# main.net
KiCad netlist of a schematic drawn in Altium Designer
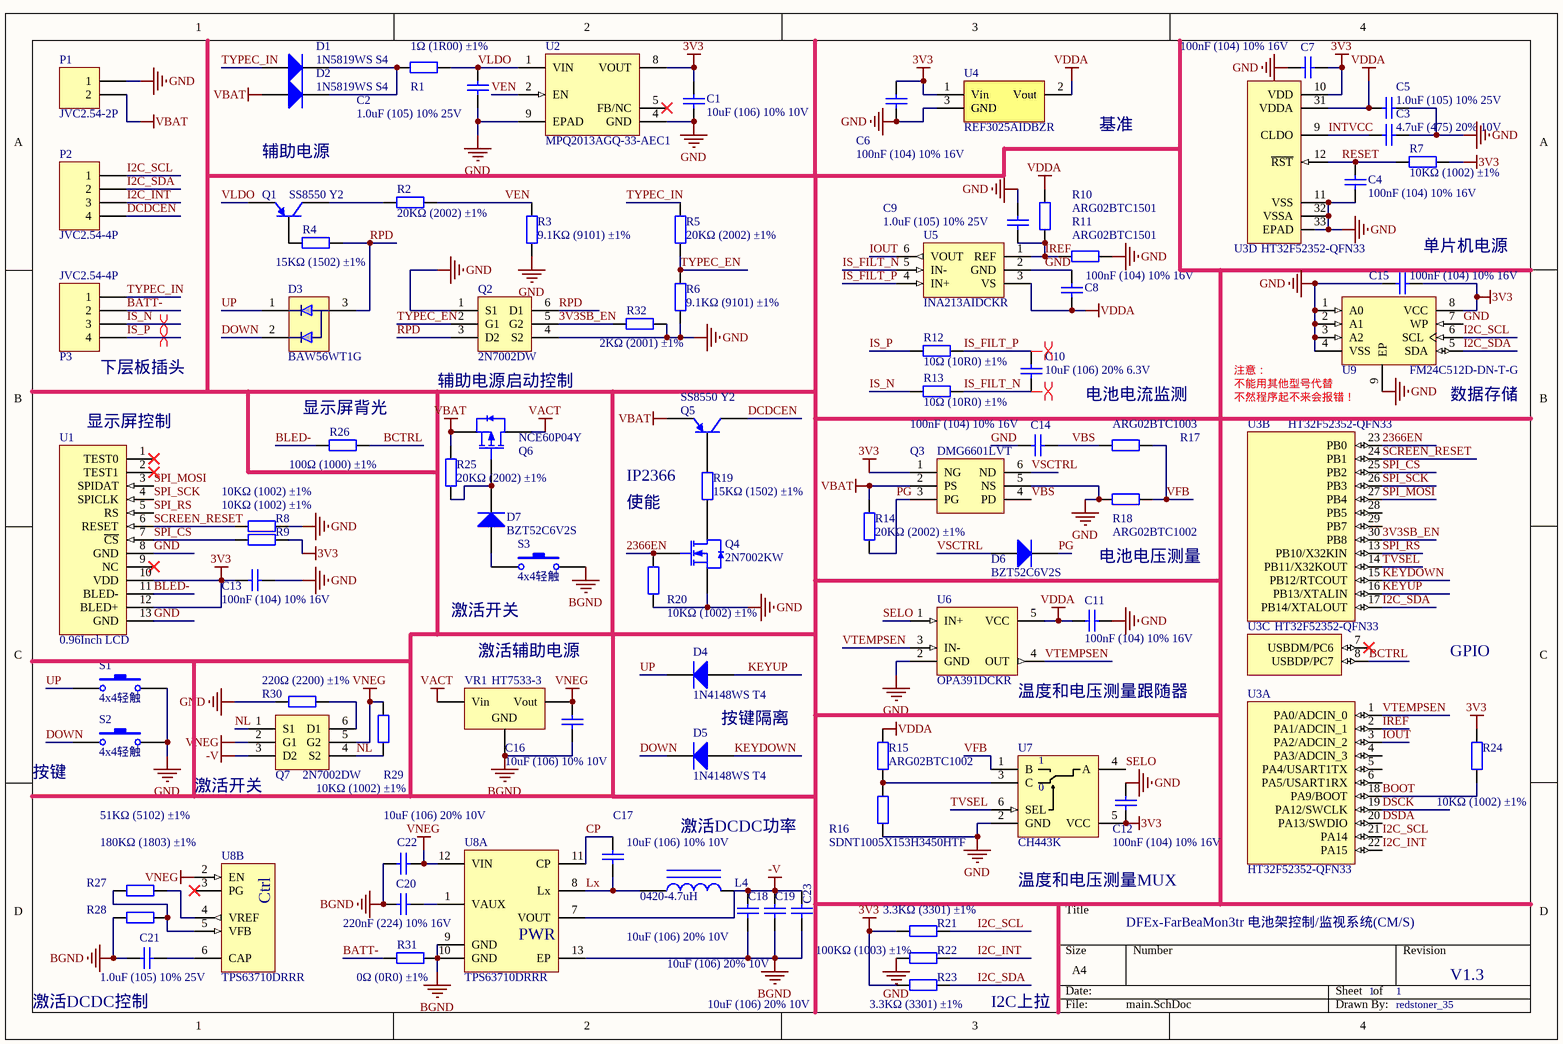
[diagram p0: main.SchDoc]

(export (version "E")
  (design (tool "Eeschema 10.0.6"))
  (components
    (comp (ref "C1")
      (value "10uF (106) 10% 10V")
      (footprint "0603_C")
      (description "贴片电容")
      (libsource (lib "Miscellaneous Devices LC") (part "0603 10uF (106) 10% 10V"))
    )
    (comp (ref "C2")
      (value "1.0uF (105) 10% 25V")
      (footprint "0402_C")
      (description "贴片电容")
      (libsource (lib "Miscellaneous Devices LC") (part "0402 1.0uF (105) 10% 25V"))
    )
    (comp (ref "C3")
      (value "4.7uF (475) 20% 10V")
      (footprint "0402_C")
      (description "贴片电容")
      (libsource (lib "Miscellaneous Devices LC") (part "0402 4.7uF (475) 20% 10V"))
    )
    (comp (ref "C4")
      (value "100nF (104) 10% 16V")
      (footprint "0402_C")
      (description "贴片电容")
      (libsource (lib "Miscellaneous Devices LC") (part "0402 100nF (104) 10% 16V"))
    )
    (comp (ref "C5")
      (value "1.0uF (105) 10% 25V")
      (footprint "0402_C")
      (description "贴片电容")
      (libsource (lib "Miscellaneous Devices LC") (part "0402 1.0uF (105) 10% 25V"))
    )
    (comp (ref "C6")
      (value "100nF (104) 10% 16V")
      (footprint "0402_C")
      (description "贴片电容")
      (libsource (lib "Miscellaneous Devices LC") (part "0402 100nF (104) 10% 16V"))
    )
    (comp (ref "C7")
      (value "100nF (104) 10% 16V")
      (footprint "0402_C")
      (description "贴片电容")
      (libsource (lib "Miscellaneous Devices LC") (part "0402 100nF (104) 10% 16V"))
    )
    (comp (ref "C8")
      (value "100nF (104) 10% 16V")
      (footprint "0402_C")
      (description "贴片电容")
      (libsource (lib "Miscellaneous Devices LC") (part "0402 100nF (104) 10% 16V"))
    )
    (comp (ref "C9")
      (value "1.0uF (105) 10% 25V")
      (footprint "0402_C")
      (description "贴片电容")
      (libsource (lib "Miscellaneous Devices LC") (part "0402 1.0uF (105) 10% 25V"))
    )
    (comp (ref "C10")
      (value "10uF (106) 20% 6.3V")
      (footprint "0402_C")
      (description "贴片电容")
      (libsource (lib "Miscellaneous Devices LC") (part "0402 10uF (106) 20% 6.3V"))
    )
    (comp (ref "C11")
      (value "100nF (104) 10% 16V")
      (footprint "0402_C")
      (description "贴片电容")
      (libsource (lib "Miscellaneous Devices LC") (part "0402 100nF (104) 10% 16V"))
    )
    (comp (ref "C12")
      (value "100nF (104) 10% 16V")
      (footprint "0402_C")
      (description "贴片电容")
      (libsource (lib "Miscellaneous Devices LC") (part "0402 100nF (104) 10% 16V"))
    )
    (comp (ref "C13")
      (value "100nF (104) 10% 16V")
      (footprint "0402_C")
      (description "贴片电容")
      (libsource (lib "Miscellaneous Devices LC") (part "0402 100nF (104) 10% 16V"))
    )
    (comp (ref "C14")
      (value "100nF (104) 10% 16V")
      (footprint "0402_C")
      (description "贴片电容")
      (libsource (lib "Miscellaneous Devices LC") (part "0402 100nF (104) 10% 16V"))
    )
    (comp (ref "C15")
      (value "100nF (104) 10% 16V")
      (footprint "0402_C")
      (description "贴片电容")
      (libsource (lib "Miscellaneous Devices LC") (part "0402 100nF (104) 10% 16V"))
    )
    (comp (ref "C16")
      (value "10uF (106) 10% 10V")
      (footprint "0603_C")
      (description "贴片电容")
      (libsource (lib "Miscellaneous Devices LC") (part "0603 10uF (106) 10% 10V"))
    )
    (comp (ref "C17")
      (value "10uF (106) 10% 10V")
      (footprint "0603_C")
      (description "贴片电容")
      (libsource (lib "Miscellaneous Devices LC") (part "0603 10uF (106) 10% 10V"))
    )
    (comp (ref "C18")
      (value "10uF (106) 20% 10V")
      (footprint "0402_C")
      (description "贴片电容")
      (libsource (lib "Miscellaneous Devices LC") (part "0402 10uF (106) 20% 6.3V"))
    )
    (comp (ref "C19")
      (value "10uF (106) 20% 10V")
      (footprint "0402_C")
      (description "贴片电容")
      (libsource (lib "Miscellaneous Devices LC") (part "0402 10uF (106) 20% 6.3V"))
    )
    (comp (ref "C20")
      (value "220nF (224) 10% 16V")
      (footprint "0402_C")
      (description "贴片电容")
      (libsource (lib "Miscellaneous Devices LC") (part "0402 220nF (224) 10% 16V"))
    )
    (comp (ref "C21")
      (value "1.0uF (105) 10% 25V")
      (footprint "0402_C")
      (description "贴片电容")
      (libsource (lib "Miscellaneous Devices LC") (part "0402 1.0uF (105) 10% 25V"))
    )
    (comp (ref "C22")
      (value "10uF (106) 20% 10V")
      (footprint "0402_C")
      (description "贴片电容")
      (libsource (lib "Miscellaneous Devices LC") (part "0402 10uF (106) 20% 6.3V"))
    )
    (comp (ref "C23")
      (value "10uF (106) 20% 10V")
      (footprint "0402_C")
      (description "贴片电容")
      (libsource (lib "Miscellaneous Devices LC") (part "0402 10uF (106) 20% 6.3V"))
    )
    (comp (ref "D1")
      (value "1N5819WS S4")
      (footprint "SOD-323")
      (description "二极管")
      (libsource (lib "Miscellaneous Devices LC") (part "SOD-323 1N4148WS T4"))
    )
    (comp (ref "D2")
      (value "1N5819WS S4")
      (footprint "SOD-323")
      (description "二极管")
      (libsource (lib "Miscellaneous Devices LC") (part "SOD-323 1N4148WS T4"))
    )
    (comp (ref "D3")
      (value "BAW56WT1G")
      (footprint "SC70-3")
      (description "Dual Switching diode,common anode,SOT323-3(SC70-3)")
      (libsource (lib "custom") (part "BAW56WT1G"))
    )
    (comp (ref "D4")
      (value "1N4148WS T4")
      (footprint "SOD-323")
      (description "二极管")
      (libsource (lib "Miscellaneous Devices LC") (part "SOD-323 1N4148WS T4"))
    )
    (comp (ref "D5")
      (value "1N4148WS T4")
      (footprint "SOD-323")
      (description "二极管")
      (libsource (lib "Miscellaneous Devices LC") (part "SOD-323 1N4148WS T4"))
    )
    (comp (ref "D6")
      (value "BZT52C6V2S")
      (footprint "SOD-323")
      (description "SOD-323稳压二极管 6.2V稳压电压")
      (libsource (lib "Miscellaneous Devices LC") (part "SOD-323 1N4148WS T4"))
    )
    (comp (ref "D7")
      (value "BZT52C6V2S")
      (footprint "SOD-323")
      (description "SOD-323稳压二极管 6.2V稳压电压")
      (libsource (lib "Miscellaneous Devices LC") (part "SOD-323 1N4148WS T4"))
    )
    (comp (ref "L4")
      (value "0420-4.7uH")
      (footprint "0420CDMCCDS-***MC")
      (description "一体成型贴片电感 4x4x2mm尺寸   4.7uH电感量")
      (fields (field (name "PUBLISHER") "Altium Limited"))
      (libsource (lib "Miscellaneous Devices") (part "Inductor Iron"))
    )
    (comp (ref "P1")
      (value "JVC2.54-2P")
      (footprint "CONN-TH_2P-P2.54_JVC-2.54MM-2P")
      (description "2-Pin")
      (fields (field (name "PUBLISHER") "Altium Limited"))
      (libsource (lib "山猫的集成库20190318") (part "CON 2"))
    )
    (comp (ref "P2")
      (value "JVC2.54-4P")
      (footprint "CONN-TH_4P-P2.54_JVC-2.54MM-4P")
      (description "4-Pin")
      (fields (field (name "PUBLISHER") "Altium Limited"))
      (libsource (lib "山猫的集成库20190318") (part "CON 4"))
    )
    (comp (ref "P3")
      (value "JVC2.54-4P")
      (footprint "CONN-TH_4P-P2.54_JVC-2.54MM-4P")
      (description "4-Pin")
      (fields (field (name "PUBLISHER") "Altium Limited"))
      (libsource (lib "山猫的集成库20190318") (part "CON 4"))
    )
    (comp (ref "Q1")
      (value "SS8550 Y2")
      (footprint "SC70-3")
      (description "PNP三极管，SOT-323 封装")
      (libsource (lib "Miscellaneous Devices LC") (part "SOT-23 SS8550 Y2"))
    )
    (comp (ref "Q2")
      (value "2N7002DW")
      (footprint "SC70-6")
      (description "Dual N-Channel MOSFET 60V340mA SOT-363")
      (libsource (lib "custom") (part "2N7002DW"))
    )
    (comp (ref "Q3")
      (value "DMG6601LVT")
      (footprint "SOT95P245X110-6N")
      (description "SOT23-6 N+P Ch. MOSFET")
      (libsource (lib "custom") (part "DMG6601LVT"))
    )
    (comp (ref "Q4")
      (value "2N7002KW")
      (footprint "SC70-3")
      (description "MOS(场效应管)")
      (libsource (lib "Miscellaneous Devices LC") (part "2N7002 7002"))
    )
    (comp (ref "Q5")
      (value "SS8550 Y2")
      (footprint "SC70-3")
      (description "PNP三极管，SOT-323 封装")
      (libsource (lib "Miscellaneous Devices LC") (part "SOT-23 SS8550 Y2"))
    )
    (comp (ref "Q6")
      (value "NCE60P04Y")
      (footprint "SOT-23(SOT-23-3)")
      (description "MOS(场效应管)")
      (libsource (lib "Miscellaneous Devices LC") (part "SI2301CDS-T1-GE3"))
    )
    (comp (ref "Q7")
      (value "2N7002DW")
      (footprint "SC70-6")
      (description "Dual N-Channel MOSFET 60V340mA SOT-363")
      (libsource (lib "custom") (part "2N7002DW"))
    )
    (comp (ref "R1")
      (value "1Ω (1R00) ±1%")
      (footprint "0402_R")
      (description "贴片电阻")
      (libsource (lib "Miscellaneous Devices LC") (part "0402 1Ω (1R00) 1%"))
    )
    (comp (ref "R2")
      (value "20KΩ (2002) ±1%")
      (footprint "0402_R")
      (description "贴片电阻")
      (libsource (lib "Miscellaneous Devices LC") (part "0402 20KΩ (2002) 1%"))
    )
    (comp (ref "R3")
      (value "9.1KΩ (9101) ±1%")
      (footprint "0402_R")
      (description "贴片电阻")
      (libsource (lib "") (part "0402 10KΩ (1002) 1%_1"))
    )
    (comp (ref "R4")
      (value "15KΩ (1502) ±1%")
      (footprint "0402_R")
      (description "贴片电阻")
      (libsource (lib "") (part "0402 15KΩ (1502) 1%_1"))
    )
    (comp (ref "R5")
      (value "20KΩ (2002) ±1%")
      (footprint "0402_R")
      (description "贴片电阻")
      (libsource (lib "") (part "0402 20KΩ (2002) 1%_1"))
    )
    (comp (ref "R6")
      (value "9.1KΩ (9101) ±1%")
      (footprint "0402_R")
      (description "贴片电阻")
      (libsource (lib "") (part "0402 10KΩ (1002) 1%_1"))
    )
    (comp (ref "R7")
      (value "10KΩ (1002) ±1%")
      (footprint "0402_R")
      (description "贴片电阻")
      (libsource (lib "Miscellaneous Devices LC") (part "0402 10KΩ (1002) 1%"))
    )
    (comp (ref "R8")
      (value "10KΩ (1002) ±1%")
      (footprint "0402_R")
      (description "贴片电阻")
      (libsource (lib "Miscellaneous Devices LC") (part "0402 10KΩ (1002) 1%"))
    )
    (comp (ref "R9")
      (value "10KΩ (1002) ±1%")
      (footprint "0402_R")
      (description "贴片电阻")
      (libsource (lib "Miscellaneous Devices LC") (part "0402 10KΩ (1002) 1%"))
    )
    (comp (ref "R10")
      (value "ARG02BTC1501")
      (footprint "0402_R")
      (description "贴片精密电阻，1.5K 0.1% 25PPM")
      (libsource (lib "") (part "0402 2KΩ (2001) 1%_1"))
    )
    (comp (ref "R11")
      (value "ARG02BTC1501")
      (footprint "0402_R")
      (description "贴片精密电阻，1.5K 0.1% 25PPM")
      (libsource (lib "Miscellaneous Devices LC") (part "0402 2KΩ (2001) 1%"))
    )
    (comp (ref "R12")
      (value "10Ω (10R0) ±1%")
      (footprint "0402_R")
      (description "贴片电阻")
      (libsource (lib "Miscellaneous Devices LC") (part "0402 10Ω (10R0) 1%"))
    )
    (comp (ref "R13")
      (value "10Ω (10R0) ±1%")
      (footprint "0402_R")
      (description "贴片电阻")
      (libsource (lib "Miscellaneous Devices LC") (part "0402 10Ω (10R0) 1%"))
    )
    (comp (ref "R14")
      (value "20KΩ (2002) ±1%")
      (footprint "0402_R")
      (description "贴片电阻")
      (libsource (lib "") (part "0402 20KΩ (2002) 1%_1"))
    )
    (comp (ref "R15")
      (value "ARG02BTC1002")
      (footprint "0402_R")
      (description "贴片精密电阻，10K 0.1% 25PPM")
      (libsource (lib "") (part "0402 10KΩ (1002) 1%_1"))
    )
    (comp (ref "R16")
      (value "SDNT1005X153H3450HTF")
      (footprint "0402_R")
      (description "贴片热敏电阻 15K@25℃ 1% B值3450")
      (libsource (lib "") (part "0402 10KΩ (1002) 1%_1"))
    )
    (comp (ref "R17")
      (value "ARG02BTC1003")
      (footprint "0402_R")
      (description "贴片精密电阻，100K 0.1% 25PPM")
      (libsource (lib "Miscellaneous Devices LC") (part "0402 100KΩ (1003) 1%"))
    )
    (comp (ref "R18")
      (value "ARG02BTC1002")
      (footprint "0402_R")
      (description "贴片精密电阻，10K 0.1% 25PPM")
      (libsource (lib "Miscellaneous Devices LC") (part "0402 10KΩ (1002) 1%"))
    )
    (comp (ref "R19")
      (value "15KΩ (1502) ±1%")
      (footprint "0402_R")
      (description "贴片电阻")
      (libsource (lib "Miscellaneous Devices LC") (part "0402 15KΩ (1502) 1%"))
    )
    (comp (ref "R20")
      (value "10KΩ (1002) ±1%")
      (footprint "0402_R")
      (description "贴片电阻")
      (libsource (lib "") (part "0402 10KΩ (1002) 1%_1"))
    )
    (comp (ref "R21")
      (value "3.3KΩ (3301) ±1%")
      (footprint "0402_R")
      (description "贴片电阻")
      (libsource (lib "Miscellaneous Devices LC") (part "0402 3.3KΩ (3301) 1%"))
    )
    (comp (ref "R22")
      (value "100KΩ (1003) ±1%")
      (footprint "0402_R")
      (description "贴片电阻")
      (libsource (lib "") (part "0402 100KΩ (1003) 1%_1"))
    )
    (comp (ref "R23")
      (value "3.3KΩ (3301) ±1%")
      (footprint "0402_R")
      (description "贴片电阻")
      (libsource (lib "Miscellaneous Devices LC") (part "0402 3.3KΩ (3301) 1%"))
    )
    (comp (ref "R24")
      (value "10KΩ (1002) ±1%")
      (footprint "0402_R")
      (description "贴片电阻")
      (libsource (lib "") (part "0402 10KΩ (1002) 1%_1"))
    )
    (comp (ref "R25")
      (value "20KΩ (2002) ±1%")
      (footprint "0402_R")
      (description "贴片电阻")
      (libsource (lib "") (part "0402 20KΩ (2002) 1%_1"))
    )
    (comp (ref "R26")
      (value "100Ω (1000) ±1%")
      (footprint "0402_R")
      (description "贴片电阻")
      (libsource (lib "Miscellaneous Devices LC") (part "0402 100Ω (1000) 1%"))
    )
    (comp (ref "R27")
      (value "51KΩ (5102) ±1%")
      (footprint "0402_R")
      (description "贴片电阻")
      (libsource (lib "Miscellaneous Devices LC") (part "0402 51KΩ (5102) 1%"))
    )
    (comp (ref "R28")
      (value "180KΩ (1803) ±1%")
      (footprint "0402_R")
      (description "贴片电阻")
      (libsource (lib "Miscellaneous Devices LC") (part "0402 18KΩ (1802) 1%"))
    )
    (comp (ref "R29")
      (value "10KΩ (1002) ±1%")
      (footprint "0402_R")
      (description "贴片电阻")
      (libsource (lib "") (part "0402 10KΩ (1002) 1%_1"))
    )
    (comp (ref "R30")
      (value "220Ω (2200) ±1%")
      (footprint "0603_R")
      (description "贴片电阻")
      (libsource (lib "Miscellaneous Devices LC") (part "0603 100Ω (1000) 1%"))
    )
    (comp (ref "R31")
      (value "0Ω (0R0) ±1%")
      (footprint "0402_R")
      (description "贴片电阻")
      (libsource (lib "Miscellaneous Devices LC") (part "0402 0Ω (0R0) 1%"))
    )
    (comp (ref "R32")
      (value "2KΩ (2001) ±1%")
      (footprint "0402_R")
      (description "贴片电阻")
      (libsource (lib "") (part "0402 2KΩ (2001) 1%_2"))
    )
    (comp (ref "S1")
      (value "4x4轻触")
      (footprint "SW-SMD_4P-L5.2-W5.2-P3.70-LS6.4")
      (description "Switch")
      (fields (field (name "PUBLISHER") "Altium Limited"))
      (libsource (lib "Miscellaneous Devices") (part "SW-PB"))
    )
    (comp (ref "S2")
      (value "4x4轻触")
      (footprint "SW-SMD_4P-L5.2-W5.2-P3.70-LS6.4")
      (description "Switch")
      (fields (field (name "PUBLISHER") "Altium Limited"))
      (libsource (lib "Miscellaneous Devices") (part "SW-PB"))
    )
    (comp (ref "S3")
      (value "4x4轻触")
      (footprint "SW-SMD_4P-L5.2-W5.2-P3.70-LS6.4")
      (description "Switch")
      (fields (field (name "PUBLISHER") "Altium Limited"))
      (libsource (lib "Miscellaneous Devices") (part "SW-PB"))
    )
    (comp (ref "U1")
      (value "0.96Inch LCD")
      (footprint "0.96\"IPS168*80TFT")
      (description "中景园电子0.96寸TFT LCD,160*80分辨率，IPS材质，ST7735控制器，SPI接口")
      (libsource (lib "custom") (part "0.96Inch LCD"))
    )
    (comp (ref "U2")
      (value "MPQ2013AGQ-33-AEC1")
      (footprint "MPQ2013A-QFN8")
      (description "具有使能引脚的40V耐压MPS LDO,   3.3V固定输出，SON-8(3x3)封装，符合AEC-Q100认证")
      (libsource (lib "custom") (part "MPQ2013AGQ-xx-AEC1"))
    )
    (comp (ref "U3")
      (value "HT32F52352-QFN33")
      (footprint "QFN32-HT32")
      (description "Holtek MCU Cortex M0+ 48MHz 128K ROM 16K RAM")
      (libsource (lib "custom") (part "HT32F52352-QFN"))
    )
    (comp (ref "U4")
      (value "REF3025AIDBZR")
      (footprint "SOT-23_N")
      (description "'50PPM/℃ 25mA最大输出能力 2.5V固定电压串联基准芯片，SOT23-3封装")
      (libsource (lib "custom") (part "REF2930"))
    )
    (comp (ref "U5")
      (value "INA213AIDCKR")
      (footprint "SC70-6")
      (description "50倍增益 26V共模范围高精度检流放大器，SC70-6封装")
      (libsource (lib "custom") (part "INA199A2DCKR"))
    )
    (comp (ref "U6")
      (value "OPA391DCKR")
      (footprint "SC70-5")
      (description "CMOS超小型单路轨到轨精密运算放  大器，45uV失调电压，SC70-5")
      (libsource (lib "custom") (part "LMV321IDCKR"))
    )
    (comp (ref "U7")
      (value "CH443K")
      (footprint "SC70-6")
      (description "Low-Voltage Analog Switch SPDT,1.8-5V Power")
      (libsource (lib "custom") (part "NC7SB3157P6X"))
    )
    (comp (ref "U8")
      (value "TPS63710DRRR")
      (footprint "DR0012C")
      (description "TI电压反相器，SON12封装")
      (libsource (lib "custom") (part "TPS63710DRRR"))
    )
    (comp (ref "U9")
      (value "FM24C512D-DN-T-G")
      (footprint "UDFN-8")
      (description "512Kbit(64K*8)I2C接口EEPROM，带有唯一ID和安全扇区 UDFN-8(2x3)")
      (libsource (lib "custom") (part "CAT24C512HU5"))
    )
    (comp (ref "VR1")
      (value "HT7533-3")
      (footprint "SOT-89(SOT-89-3)")
      (description "低压差线性稳压(LDO)")
      (libsource (lib "Miscellaneous Devices LC") (part "SOT-89 HT7550-1"))
    )
  )
  (nets
    (net (code "1") (name "-V") (class "Default")
      (node (ref "C18") (pin "2") (pinfunction "2_2") (pintype "passive"))
      (node (ref "C19") (pin "2") (pinfunction "2_2") (pintype "passive"))
      (node (ref "C23") (pin "2") (pinfunction "2_2") (pintype "passive"))
      (node (ref "L4") (pin "2") (pinfunction "2_2") (pintype "passive"))
      (node (ref "Q7") (pin "3") (pinfunction "D2_3") (pintype "passive"))
      (node (ref "U8") (pin "7") (pinfunction "VOUT_7") (pintype "power_in"))
    )
    (net (code "2") (name "/3V3SB_EN") (class "Default")
      (node (ref "Q2") (pin "5") (pinfunction "G2_5") (pintype "passive"))
      (node (ref "R32") (pin "1") (pinfunction "1_1") (pintype "passive"))
      (node (ref "U3") (pin "30") (pinfunction "PB8_30") (pintype "bidirectional"))
    )
    (net (code "3") (name "/2366EN") (class "Default")
      (node (ref "Q4") (pin "1") (pinfunction "G_1") (pintype "passive"))
      (node (ref "R20") (pin "2") (pinfunction "2_2") (pintype "passive"))
      (node (ref "U3") (pin "23") (pinfunction "PB0_23") (pintype "bidirectional"))
    )
    (net (code "4") (name "/BATT-") (class "Default")
      (node (ref "P3") (pin "2") (pinfunction "2_2") (pintype "passive"))
      (node (ref "R31") (pin "1") (pinfunction "1_1") (pintype "passive"))
    )
    (net (code "5") (name "/BCTRL") (class "Default")
      (node (ref "R26") (pin "1") (pinfunction "1_1") (pintype "passive"))
      (node (ref "U3") (pin "8") (pinfunction "USBDP/PC7_8") (pintype "bidirectional"))
    )
    (net (code "6") (name "/BLED-") (class "Default")
      (node (ref "R26") (pin "2") (pinfunction "2_2") (pintype "passive"))
      (node (ref "U1") (pin "11") (pinfunction "BLED-_11") (pintype "power_in"))
    )
    (net (code "7") (name "/BOOT") (class "Default")
      (node (ref "R24") (pin "1") (pinfunction "1_1") (pintype "passive"))
      (node (ref "U3") (pin "18") (pinfunction "PA9/BOOT_18") (pintype "bidirectional"))
    )
    (net (code "8") (name "/CP") (class "Default")
      (node (ref "C17") (pin "2") (pinfunction "2_2") (pintype "passive"))
      (node (ref "U8") (pin "11") (pinfunction "CP_11") (pintype "power_in"))
    )
    (net (code "9") (name "/DCDCEN") (class "Default")
      (node (ref "P2") (pin "4") (pinfunction "4_4") (pintype "passive"))
      (node (ref "Q5") (pin "3") (pinfunction "C_3") (pintype "passive"))
    )
    (net (code "10") (name "/DOWN") (class "Default")
      (node (ref "D3") (pin "2") (pinfunction "K2_2") (pintype "passive"))
      (node (ref "D5") (pin "2") (pinfunction "K_2") (pintype "passive"))
      (node (ref "S2") (pin "1") (pinfunction "1_1") (pintype "passive"))
    )
    (net (code "11") (name "/DSCK") (class "Default")
      (node (ref "U3") (pin "19") (pinfunction "PA12/SWCLK_19") (pintype "bidirectional"))
    )
    (net (code "12") (name "/DSDA") (class "Default")
      (node (ref "U3") (pin "20") (pinfunction "PA13/SWDIO_20") (pintype "bidirectional"))
    )
    (net (code "13") (name "/I2C_INT") (class "Default")
      (node (ref "P2") (pin "3") (pinfunction "3_3") (pintype "passive"))
      (node (ref "R22") (pin "2") (pinfunction "2_2") (pintype "passive"))
      (node (ref "U3") (pin "22") (pinfunction "PA15_22") (pintype "bidirectional"))
    )
    (net (code "14") (name "/I2C_SCL") (class "Default")
      (node (ref "P2") (pin "1") (pinfunction "1_1") (pintype "passive"))
      (node (ref "R21") (pin "2") (pinfunction "2_2") (pintype "passive"))
      (node (ref "U3") (pin "21") (pinfunction "PA14_21") (pintype "bidirectional"))
      (node (ref "U9") (pin "6") (pinfunction "SCL_6") (pintype "input"))
    )
    (net (code "15") (name "/I2C_SDA") (class "Default")
      (node (ref "P2") (pin "2") (pinfunction "2_2") (pintype "passive"))
      (node (ref "R23") (pin "2") (pinfunction "2_2") (pintype "passive"))
      (node (ref "U3") (pin "17") (pinfunction "PB14/XTALOUT_17") (pintype "bidirectional"))
      (node (ref "U9") (pin "5") (pinfunction "SDA_5") (pintype "bidirectional"))
    )
    (net (code "16") (name "/INTVCC") (class "Default")
      (node (ref "C3") (pin "1") (pinfunction "1_1") (pintype "passive"))
      (node (ref "U3") (pin "9") (pinfunction "CLDO_9") (pintype "power_in"))
    )
    (net (code "17") (name "/IOUT") (class "Default")
      (node (ref "U3") (pin "3") (pinfunction "PA2/ADCIN_2_3") (pintype "bidirectional"))
      (node (ref "U5") (pin "6") (pinfunction "VOUT_6") (pintype "output"))
    )
    (net (code "18") (name "/IREF") (class "Default")
      (node (ref "C9") (pin "1") (pinfunction "1_1") (pintype "passive"))
      (node (ref "R10") (pin "1") (pinfunction "1_1") (pintype "passive"))
      (node (ref "R11") (pin "2") (pinfunction "2_2") (pintype "passive"))
      (node (ref "U3") (pin "2") (pinfunction "PA1/ADCIN_1_2") (pintype "bidirectional"))
      (node (ref "U5") (pin "1") (pinfunction "REF_1") (pintype "passive"))
    )
    (net (code "19") (name "/IS_FILT_N") (class "Default")
      (node (ref "C10") (pin "1") (pinfunction "1_1") (pintype "passive"))
      (node (ref "R13") (pin "2") (pinfunction "2_2") (pintype "passive"))
      (node (ref "U5") (pin "5") (pinfunction "IN-_5") (pintype "input"))
    )
    (net (code "20") (name "/IS_FILT_P") (class "Default")
      (node (ref "C10") (pin "2") (pinfunction "2_2") (pintype "passive"))
      (node (ref "R12") (pin "2") (pinfunction "2_2") (pintype "passive"))
      (node (ref "U5") (pin "4") (pinfunction "IN+_4") (pintype "input"))
    )
    (net (code "21") (name "/IS_N") (class "Default")
      (node (ref "P3") (pin "3") (pinfunction "3_3") (pintype "passive"))
      (node (ref "R13") (pin "1") (pinfunction "1_1") (pintype "passive"))
    )
    (net (code "22") (name "/IS_P") (class "Default")
      (node (ref "P3") (pin "4") (pinfunction "4_4") (pintype "passive"))
      (node (ref "R12") (pin "1") (pinfunction "1_1") (pintype "passive"))
    )
    (net (code "23") (name "/KEYDOWN") (class "Default")
      (node (ref "D5") (pin "1") (pinfunction "A_1") (pintype "passive"))
      (node (ref "U3") (pin "15") (pinfunction "PB12/RTCOUT_15") (pintype "bidirectional"))
    )
    (net (code "24") (name "/KEYUP") (class "Default")
      (node (ref "D4") (pin "1") (pinfunction "A_1") (pintype "passive"))
      (node (ref "U3") (pin "16") (pinfunction "PB13/XTALIN_16") (pintype "bidirectional"))
    )
    (net (code "25") (name "/Lx") (class "Default")
      (node (ref "C17") (pin "1") (pinfunction "1_1") (pintype "passive"))
      (node (ref "L4") (pin "1") (pinfunction "1_1") (pintype "passive"))
      (node (ref "U8") (pin "8") (pinfunction "Lx_8") (pintype "power_in"))
    )
    (net (code "26") (name "/NL") (class "Default")
      (node (ref "Q7") (pin "1") (pinfunction "S1_1") (pintype "passive"))
      (node (ref "Q7") (pin "4") (pinfunction "S2_4") (pintype "passive"))
      (node (ref "R29") (pin "1") (pinfunction "1_1") (pintype "passive"))
    )
    (net (code "27") (name "/PG") (class "Default")
      (node (ref "D6") (pin "2") (pinfunction "K_2") (pintype "passive"))
      (node (ref "Q3") (pin "3") (pinfunction "PG_3") (pintype "passive"))
      (node (ref "R14") (pin "1") (pinfunction "1_1") (pintype "passive"))
    )
    (net (code "28") (name "/RESET") (class "Default")
      (node (ref "C4") (pin "2") (pinfunction "2_2") (pintype "passive"))
      (node (ref "R7") (pin "1") (pinfunction "1_1") (pintype "passive"))
      (node (ref "U3") (pin "12") (pinfunction "~{RST}_12") (pintype "input"))
    )
    (net (code "29") (name "/RPD") (class "Default")
      (node (ref "D3") (pin "3") (pinfunction "A_3") (pintype "passive"))
      (node (ref "Q2") (pin "3") (pinfunction "D2_3") (pintype "passive"))
      (node (ref "Q2") (pin "6") (pinfunction "D1_6") (pintype "passive"))
      (node (ref "R4") (pin "2") (pinfunction "2_2") (pintype "passive"))
    )
    (net (code "30") (name "/SCREEN_RESET") (class "Default")
      (node (ref "R8") (pin "1") (pinfunction "1_1") (pintype "passive"))
      (node (ref "U1") (pin "6") (pinfunction "RESET_6") (pintype "input"))
      (node (ref "U3") (pin "24") (pinfunction "PB1_24") (pintype "bidirectional"))
    )
    (net (code "31") (name "/SELO") (class "Default")
      (node (ref "U6") (pin "1") (pinfunction "IN+_1") (pintype "input"))
      (node (ref "U7") (pin "4") (pinfunction "A_4") (pintype "passive"))
    )
    (net (code "32") (name "/SPI_CS") (class "Default")
      (node (ref "R9") (pin "1") (pinfunction "1_1") (pintype "passive"))
      (node (ref "U1") (pin "7") (pinfunction "~{CS}_7") (pintype "input"))
      (node (ref "U3") (pin "25") (pinfunction "PB2_25") (pintype "bidirectional"))
    )
    (net (code "33") (name "/SPI_MOSI") (class "Default")
      (node (ref "U1") (pin "3") (pinfunction "SPIDAT_3") (pintype "input"))
      (node (ref "U3") (pin "27") (pinfunction "PB4_27") (pintype "bidirectional"))
    )
    (net (code "34") (name "/SPI_RS") (class "Default")
      (node (ref "U1") (pin "5") (pinfunction "RS_5") (pintype "input"))
      (node (ref "U3") (pin "13") (pinfunction "PB10/X32KIN_13") (pintype "bidirectional"))
    )
    (net (code "35") (name "/SPI_SCK") (class "Default")
      (node (ref "U1") (pin "4") (pinfunction "SPICLK_4") (pintype "input"))
      (node (ref "U3") (pin "26") (pinfunction "PB3_26") (pintype "bidirectional"))
    )
    (net (code "36") (name "/TVSEL") (class "Default")
      (node (ref "U3") (pin "14") (pinfunction "PB11/X32KOUT_14") (pintype "bidirectional"))
      (node (ref "U7") (pin "6") (pinfunction "SEL_6") (pintype "input"))
    )
    (net (code "37") (name "/TYPEC_EN") (class "Default")
      (node (ref "Q2") (pin "2") (pinfunction "G1_2") (pintype "passive"))
      (node (ref "R5") (pin "1") (pinfunction "1_1") (pintype "passive"))
      (node (ref "R6") (pin "2") (pinfunction "2_2") (pintype "passive"))
    )
    (net (code "38") (name "/TYPEC_IN") (class "Default")
      (node (ref "D1") (pin "1") (pinfunction "A_1") (pintype "passive"))
      (node (ref "P3") (pin "1") (pinfunction "1_1") (pintype "passive"))
      (node (ref "R5") (pin "2") (pinfunction "2_2") (pintype "passive"))
    )
    (net (code "39") (name "/UP") (class "Default")
      (node (ref "D3") (pin "1") (pinfunction "K1_1") (pintype "passive"))
      (node (ref "D4") (pin "2") (pinfunction "K_2") (pintype "passive"))
      (node (ref "S1") (pin "1") (pinfunction "1_1") (pintype "passive"))
    )
    (net (code "40") (name "/VBS") (class "Default")
      (node (ref "C14") (pin "1") (pinfunction "1_1") (pintype "passive"))
      (node (ref "Q3") (pin "4") (pinfunction "PD_4") (pintype "passive"))
      (node (ref "R17") (pin "2") (pinfunction "2_2") (pintype "passive"))
    )
    (net (code "41") (name "/VEN") (class "Default")
      (node (ref "R2") (pin "2") (pinfunction "2_2") (pintype "passive"))
      (node (ref "R3") (pin "2") (pinfunction "2_2") (pintype "passive"))
      (node (ref "U2") (pin "2") (pinfunction "EN_2") (pintype "input"))
    )
    (net (code "42") (name "/VFB") (class "Default")
      (node (ref "R17") (pin "1") (pinfunction "1_1") (pintype "passive"))
      (node (ref "R18") (pin "2") (pinfunction "2_2") (pintype "passive"))
      (node (ref "U7") (pin "1") (pinfunction "B_1") (pintype "passive"))
    )
    (net (code "43") (name "/VLDO") (class "Default")
      (node (ref "C2") (pin "2") (pinfunction "2_2") (pintype "passive"))
      (node (ref "Q1") (pin "2") (pinfunction "E_2") (pintype "passive"))
      (node (ref "R1") (pin "2") (pinfunction "2_2") (pintype "passive"))
      (node (ref "U2") (pin "1") (pinfunction "VIN_1") (pintype "power_in"))
    )
    (net (code "44") (name "/VSCTRL") (class "Default")
      (node (ref "D6") (pin "1") (pinfunction "A_1") (pintype "passive"))
      (node (ref "Q3") (pin "6") (pinfunction "ND_6") (pintype "passive"))
    )
    (net (code "45") (name "/VTEMPSEN") (class "Default")
      (node (ref "U3") (pin "1") (pinfunction "PA0/ADCIN_0_1") (pintype "bidirectional"))
      (node (ref "U6") (pin "3") (pinfunction "IN-_3") (pintype "input"))
      (node (ref "U6") (pin "4") (pinfunction "OUT_4") (pintype "output"))
    )
    (net (code "46") (name "3V3") (class "Default")
      (node (ref "C1") (pin "2") (pinfunction "2_2") (pintype "passive"))
      (node (ref "C12") (pin "2") (pinfunction "2_2") (pintype "passive"))
      (node (ref "C13") (pin "1") (pinfunction "1_1") (pintype "passive"))
      (node (ref "C15") (pin "2") (pinfunction "2_2") (pintype "passive"))
      (node (ref "C6") (pin "2") (pinfunction "2_2") (pintype "passive"))
      (node (ref "C7") (pin "2") (pinfunction "2_2") (pintype "passive"))
      (node (ref "Q3") (pin "1") (pinfunction "NG_1") (pintype "passive"))
      (node (ref "R21") (pin "1") (pinfunction "1_1") (pintype "passive"))
      (node (ref "R23") (pin "1") (pinfunction "1_1") (pintype "passive"))
      (node (ref "R24") (pin "2") (pinfunction "2_2") (pintype "passive"))
      (node (ref "R7") (pin "2") (pinfunction "2_2") (pintype "passive"))
      (node (ref "R9") (pin "2") (pinfunction "2_2") (pintype "passive"))
      (node (ref "U1") (pin "10") (pinfunction "VDD_10") (pintype "power_in"))
      (node (ref "U1") (pin "12") (pinfunction "BLED+_12") (pintype "power_in"))
      (node (ref "U2") (pin "8") (pinfunction "VOUT_8") (pintype "passive"))
      (node (ref "U3") (pin "10") (pinfunction "VDD_10") (pintype "power_in"))
      (node (ref "U4") (pin "1") (pinfunction "Vin_1") (pintype "passive"))
      (node (ref "U7") (pin "5") (pinfunction "VCC_5") (pintype "power_in"))
      (node (ref "U9") (pin "8") (pinfunction "VCC_8") (pintype "power_in"))
    )
    (net (code "47") (name "BGND") (class "Default")
      (node (ref "C16") (pin "1") (pinfunction "1_1") (pintype "passive"))
      (node (ref "C18") (pin "1") (pinfunction "1_1") (pintype "passive"))
      (node (ref "C19") (pin "1") (pinfunction "1_1") (pintype "passive"))
      (node (ref "C20") (pin "1") (pinfunction "1_1") (pintype "passive"))
      (node (ref "C21") (pin "1") (pinfunction "1_1") (pintype "passive"))
      (node (ref "C22") (pin "1") (pinfunction "1_1") (pintype "passive"))
      (node (ref "C23") (pin "1") (pinfunction "1_1") (pintype "passive"))
      (node (ref "R28") (pin "1") (pinfunction "1_1") (pintype "passive"))
      (node (ref "R31") (pin "2") (pinfunction "2_2") (pintype "passive"))
      (node (ref "S3") (pin "2") (pinfunction "2_2") (pintype "passive"))
      (node (ref "U8") (pin "10") (pinfunction "GND_10") (pintype "power_in"))
      (node (ref "U8") (pin "13") (pinfunction "EP_13") (pintype "power_in"))
      (node (ref "U8") (pin "9") (pinfunction "GND_9") (pintype "power_in"))
      (node (ref "VR1") (pin "1") (pinfunction "GND_1") (pintype "passive"))
    )
    (net (code "48") (name "GND") (class "Default")
      (node (ref "C1") (pin "1") (pinfunction "1_1") (pintype "passive"))
      (node (ref "C11") (pin "1") (pinfunction "1_1") (pintype "passive"))
      (node (ref "C12") (pin "1") (pinfunction "1_1") (pintype "passive"))
      (node (ref "C13") (pin "2") (pinfunction "2_2") (pintype "passive"))
      (node (ref "C14") (pin "2") (pinfunction "2_2") (pintype "passive"))
      (node (ref "C15") (pin "1") (pinfunction "1_1") (pintype "passive"))
      (node (ref "C2") (pin "1") (pinfunction "1_1") (pintype "passive"))
      (node (ref "C3") (pin "2") (pinfunction "2_2") (pintype "passive"))
      (node (ref "C4") (pin "1") (pinfunction "1_1") (pintype "passive"))
      (node (ref "C5") (pin "2") (pinfunction "2_2") (pintype "passive"))
      (node (ref "C6") (pin "1") (pinfunction "1_1") (pintype "passive"))
      (node (ref "C7") (pin "1") (pinfunction "1_1") (pintype "passive"))
      (node (ref "C8") (pin "2") (pinfunction "2_2") (pintype "passive"))
      (node (ref "C9") (pin "2") (pinfunction "2_2") (pintype "passive"))
      (node (ref "P1") (pin "1") (pinfunction "1_1") (pintype "passive"))
      (node (ref "Q2") (pin "1") (pinfunction "S1_1") (pintype "passive"))
      (node (ref "Q2") (pin "4") (pinfunction "S2_4") (pintype "passive"))
      (node (ref "Q3") (pin "5") (pinfunction "NS_5") (pintype "passive"))
      (node (ref "Q4") (pin "2") (pinfunction "S_2") (pintype "passive"))
      (node (ref "R11") (pin "1") (pinfunction "1_1") (pintype "passive"))
      (node (ref "R16") (pin "1") (pinfunction "1_1") (pintype "passive"))
      (node (ref "R18") (pin "1") (pinfunction "1_1") (pintype "passive"))
      (node (ref "R20") (pin "1") (pinfunction "1_1") (pintype "passive"))
      (node (ref "R22") (pin "1") (pinfunction "1_1") (pintype "passive"))
      (node (ref "R3") (pin "1") (pinfunction "1_1") (pintype "passive"))
      (node (ref "R30") (pin "1") (pinfunction "1_1") (pintype "passive"))
      (node (ref "R32") (pin "2") (pinfunction "2_2") (pintype "passive"))
      (node (ref "R6") (pin "1") (pinfunction "1_1") (pintype "passive"))
      (node (ref "R8") (pin "2") (pinfunction "2_2") (pintype "passive"))
      (node (ref "S1") (pin "2") (pinfunction "2_2") (pintype "passive"))
      (node (ref "S2") (pin "2") (pinfunction "2_2") (pintype "passive"))
      (node (ref "U1") (pin "13") (pinfunction "GND_13") (pintype "power_in"))
      (node (ref "U1") (pin "8") (pinfunction "GND_8") (pintype "power_in"))
      (node (ref "U2") (pin "4") (pinfunction "GND_4") (pintype "power_in"))
      (node (ref "U2") (pin "9") (pinfunction "EPAD_9") (pintype "passive"))
      (node (ref "U3") (pin "11") (pinfunction "VSS_11") (pintype "power_in"))
      (node (ref "U3") (pin "32") (pinfunction "VSSA_32") (pintype "power_in"))
      (node (ref "U3") (pin "33") (pinfunction "EPAD_33") (pintype "power_in"))
      (node (ref "U4") (pin "3") (pinfunction "GND_3") (pintype "passive"))
      (node (ref "U5") (pin "2") (pinfunction "GND_2") (pintype "passive"))
      (node (ref "U6") (pin "2") (pinfunction "GND_2") (pintype "power_in"))
      (node (ref "U7") (pin "2") (pinfunction "GND_2") (pintype "power_in"))
      (node (ref "U9") (pin "1") (pinfunction "A0_1") (pintype "input"))
      (node (ref "U9") (pin "2") (pinfunction "A1_2") (pintype "input"))
      (node (ref "U9") (pin "3") (pinfunction "A2_3") (pintype "input"))
      (node (ref "U9") (pin "4") (pinfunction "VSS_4") (pintype "power_in"))
      (node (ref "U9") (pin "7") (pinfunction "WP_7") (pintype "input"))
      (node (ref "U9") (pin "9") (pinfunction "EP_9") (pintype "power_in"))
    )
    (net (code "49") (name "Net-(D1-K)") (class "Default")
      (node (ref "D1") (pin "2") (pinfunction "K_2") (pintype "passive"))
      (node (ref "D2") (pin "2") (pinfunction "K_2") (pintype "passive"))
      (node (ref "R1") (pin "1") (pinfunction "1_1") (pintype "passive"))
    )
    (net (code "50") (name "Net-(D7-A)") (class "Default")
      (node (ref "D7") (pin "1") (pinfunction "A_1") (pintype "passive"))
      (node (ref "S3") (pin "1") (pinfunction "1_1") (pintype "passive"))
    )
    (net (code "51") (name "Net-(D7-K)") (class "Default")
      (node (ref "D7") (pin "2") (pinfunction "K_2") (pintype "passive"))
      (node (ref "Q6") (pin "1") (pinfunction "G_1") (pintype "passive"))
      (node (ref "R25") (pin "1") (pinfunction "1_1") (pintype "passive"))
    )
    (net (code "52") (name "Net-(Q1-B)") (class "Default")
      (node (ref "Q1") (pin "1") (pinfunction "B_1") (pintype "passive"))
      (node (ref "R4") (pin "1") (pinfunction "1_1") (pintype "passive"))
    )
    (net (code "53") (name "Net-(Q1-C)") (class "Default")
      (node (ref "Q1") (pin "3") (pinfunction "C_3") (pintype "passive"))
      (node (ref "R2") (pin "1") (pinfunction "1_1") (pintype "passive"))
    )
    (net (code "54") (name "Net-(Q4-D)") (class "Default")
      (node (ref "Q4") (pin "3") (pinfunction "D_3") (pintype "passive"))
      (node (ref "R19") (pin "1") (pinfunction "1_1") (pintype "passive"))
    )
    (net (code "55") (name "Net-(Q5-B)") (class "Default")
      (node (ref "Q5") (pin "1") (pinfunction "B_1") (pintype "passive"))
      (node (ref "R19") (pin "2") (pinfunction "2_2") (pintype "passive"))
    )
    (net (code "56") (name "Net-(Q7-D1)") (class "Default")
      (node (ref "Q7") (pin "6") (pinfunction "D1_6") (pintype "passive"))
      (node (ref "R30") (pin "2") (pinfunction "2_2") (pintype "passive"))
    )
    (net (code "57") (name "Net-(U7-C)") (class "Default")
      (node (ref "R15") (pin "1") (pinfunction "1_1") (pintype "passive"))
      (node (ref "R16") (pin "2") (pinfunction "2_2") (pintype "passive"))
      (node (ref "U7") (pin "3") (pinfunction "C_3") (pintype "passive"))
    )
    (net (code "58") (name "Net-(U8A-VAUX)") (class "Default")
      (node (ref "C20") (pin "2") (pinfunction "2_2") (pintype "passive"))
      (node (ref "U8") (pin "1") (pinfunction "VAUX_1") (pintype "power_in"))
    )
    (net (code "59") (name "Net-(U8B-CAP)") (class "Default")
      (node (ref "C21") (pin "2") (pinfunction "2_2") (pintype "passive"))
      (node (ref "U8") (pin "6") (pinfunction "CAP_6") (pintype "passive"))
    )
    (net (code "60") (name "Net-(U8B-VFB)") (class "Default")
      (node (ref "R27") (pin "1") (pinfunction "1_1") (pintype "passive"))
      (node (ref "R28") (pin "2") (pinfunction "2_2") (pintype "passive"))
      (node (ref "U8") (pin "5") (pinfunction "VFB_5") (pintype "input"))
    )
    (net (code "61") (name "Net-(U8B-VREF)") (class "Default")
      (node (ref "R27") (pin "2") (pinfunction "2_2") (pintype "passive"))
      (node (ref "U8") (pin "4") (pinfunction "VREF_4") (pintype "output"))
    )
    (net (code "62") (name "VACT") (class "Default")
      (node (ref "Q6") (pin "3") (pinfunction "D_3") (pintype "passive"))
      (node (ref "VR1") (pin "2") (pinfunction "Vin_2") (pintype "passive"))
    )
    (net (code "63") (name "VBAT") (class "Default")
      (node (ref "D2") (pin "1") (pinfunction "A_1") (pintype "passive"))
      (node (ref "P1") (pin "2") (pinfunction "2_2") (pintype "passive"))
      (node (ref "Q3") (pin "2") (pinfunction "PS_2") (pintype "passive"))
      (node (ref "Q5") (pin "2") (pinfunction "E_2") (pintype "passive"))
      (node (ref "Q6") (pin "2") (pinfunction "S_2") (pintype "passive"))
      (node (ref "R14") (pin "2") (pinfunction "2_2") (pintype "passive"))
      (node (ref "R25") (pin "2") (pinfunction "2_2") (pintype "passive"))
    )
    (net (code "64") (name "VDDA") (class "Default")
      (node (ref "C11") (pin "2") (pinfunction "2_2") (pintype "passive"))
      (node (ref "C5") (pin "1") (pinfunction "1_1") (pintype "passive"))
      (node (ref "C8") (pin "1") (pinfunction "1_1") (pintype "passive"))
      (node (ref "R10") (pin "2") (pinfunction "2_2") (pintype "passive"))
      (node (ref "R15") (pin "2") (pinfunction "2_2") (pintype "passive"))
      (node (ref "U3") (pin "31") (pinfunction "VDDA_31") (pintype "power_in"))
      (node (ref "U4") (pin "2") (pinfunction "Vout_2") (pintype "power_in"))
      (node (ref "U5") (pin "3") (pinfunction "VS_3") (pintype "passive"))
      (node (ref "U6") (pin "5") (pinfunction "VCC_5") (pintype "power_in"))
    )
    (net (code "65") (name "VNEG") (class "Default")
      (node (ref "C16") (pin "2") (pinfunction "2_2") (pintype "passive"))
      (node (ref "C22") (pin "2") (pinfunction "2_2") (pintype "passive"))
      (node (ref "Q7") (pin "2") (pinfunction "G1_2") (pintype "passive"))
      (node (ref "Q7") (pin "5") (pinfunction "G2_5") (pintype "passive"))
      (node (ref "R29") (pin "2") (pinfunction "2_2") (pintype "passive"))
      (node (ref "U8") (pin "12") (pinfunction "VIN_12") (pintype "power_in"))
      (node (ref "U8") (pin "2") (pinfunction "EN_2") (pintype "input"))
      (node (ref "VR1") (pin "3") (pinfunction "Vout_3") (pintype "passive"))
    )
    (net (code "66") (name "unconnected-(U1-NC-Pad9)") (class "Default")
      (node (ref "U1") (pin "9") (pinfunction "NC_9") (pintype "passive+no_connect"))
    )
    (net (code "67") (name "unconnected-(U1-TEST0-Pad1)") (class "Default")
      (node (ref "U1") (pin "1") (pinfunction "TEST0_1") (pintype "passive+no_connect"))
    )
    (net (code "68") (name "unconnected-(U1-TEST1-Pad2)") (class "Default")
      (node (ref "U1") (pin "2") (pinfunction "TEST1_2") (pintype "passive+no_connect"))
    )
    (net (code "69") (name "unconnected-(U2-FB{slash}NC-Pad5)") (class "Default")
      (node (ref "U2") (pin "5") (pinfunction "FB/NC_5") (pintype "passive+no_connect"))
    )
    (net (code "70") (name "unconnected-(U3A-PA3{slash}ADCIN_3-Pad4)") (class "Default")
      (node (ref "U3") (pin "4") (pinfunction "PA3/ADCIN_3_4") (pintype "bidirectional"))
    )
    (net (code "71") (name "unconnected-(U3A-PA4{slash}USART1TX-Pad5)") (class "Default")
      (node (ref "U3") (pin "5") (pinfunction "PA4/USART1TX_5") (pintype "bidirectional"))
    )
    (net (code "72") (name "unconnected-(U3A-PA5{slash}USART1RX-Pad6)") (class "Default")
      (node (ref "U3") (pin "6") (pinfunction "PA5/USART1RX_6") (pintype "bidirectional"))
    )
    (net (code "73") (name "unconnected-(U3B-PB5-Pad28)") (class "Default")
      (node (ref "U3") (pin "28") (pinfunction "PB5_28") (pintype "bidirectional"))
    )
    (net (code "74") (name "unconnected-(U3B-PB7-Pad29)") (class "Default")
      (node (ref "U3") (pin "29") (pinfunction "PB7_29") (pintype "bidirectional"))
    )
    (net (code "75") (name "unconnected-(U3C-USBDM{slash}PC6-Pad7)") (class "Default")
      (node (ref "U3") (pin "7") (pinfunction "USBDM/PC6_7") (pintype "bidirectional+no_connect"))
    )
    (net (code "76") (name "unconnected-(U8B-PG-Pad3)") (class "Default")
      (node (ref "U8") (pin "3") (pinfunction "PG_3") (pintype "open_collector+no_connect"))
    )
  )
)
